# 02_-Thermistors.net
KiCad netlist of a schematic drawn in Altium Designer
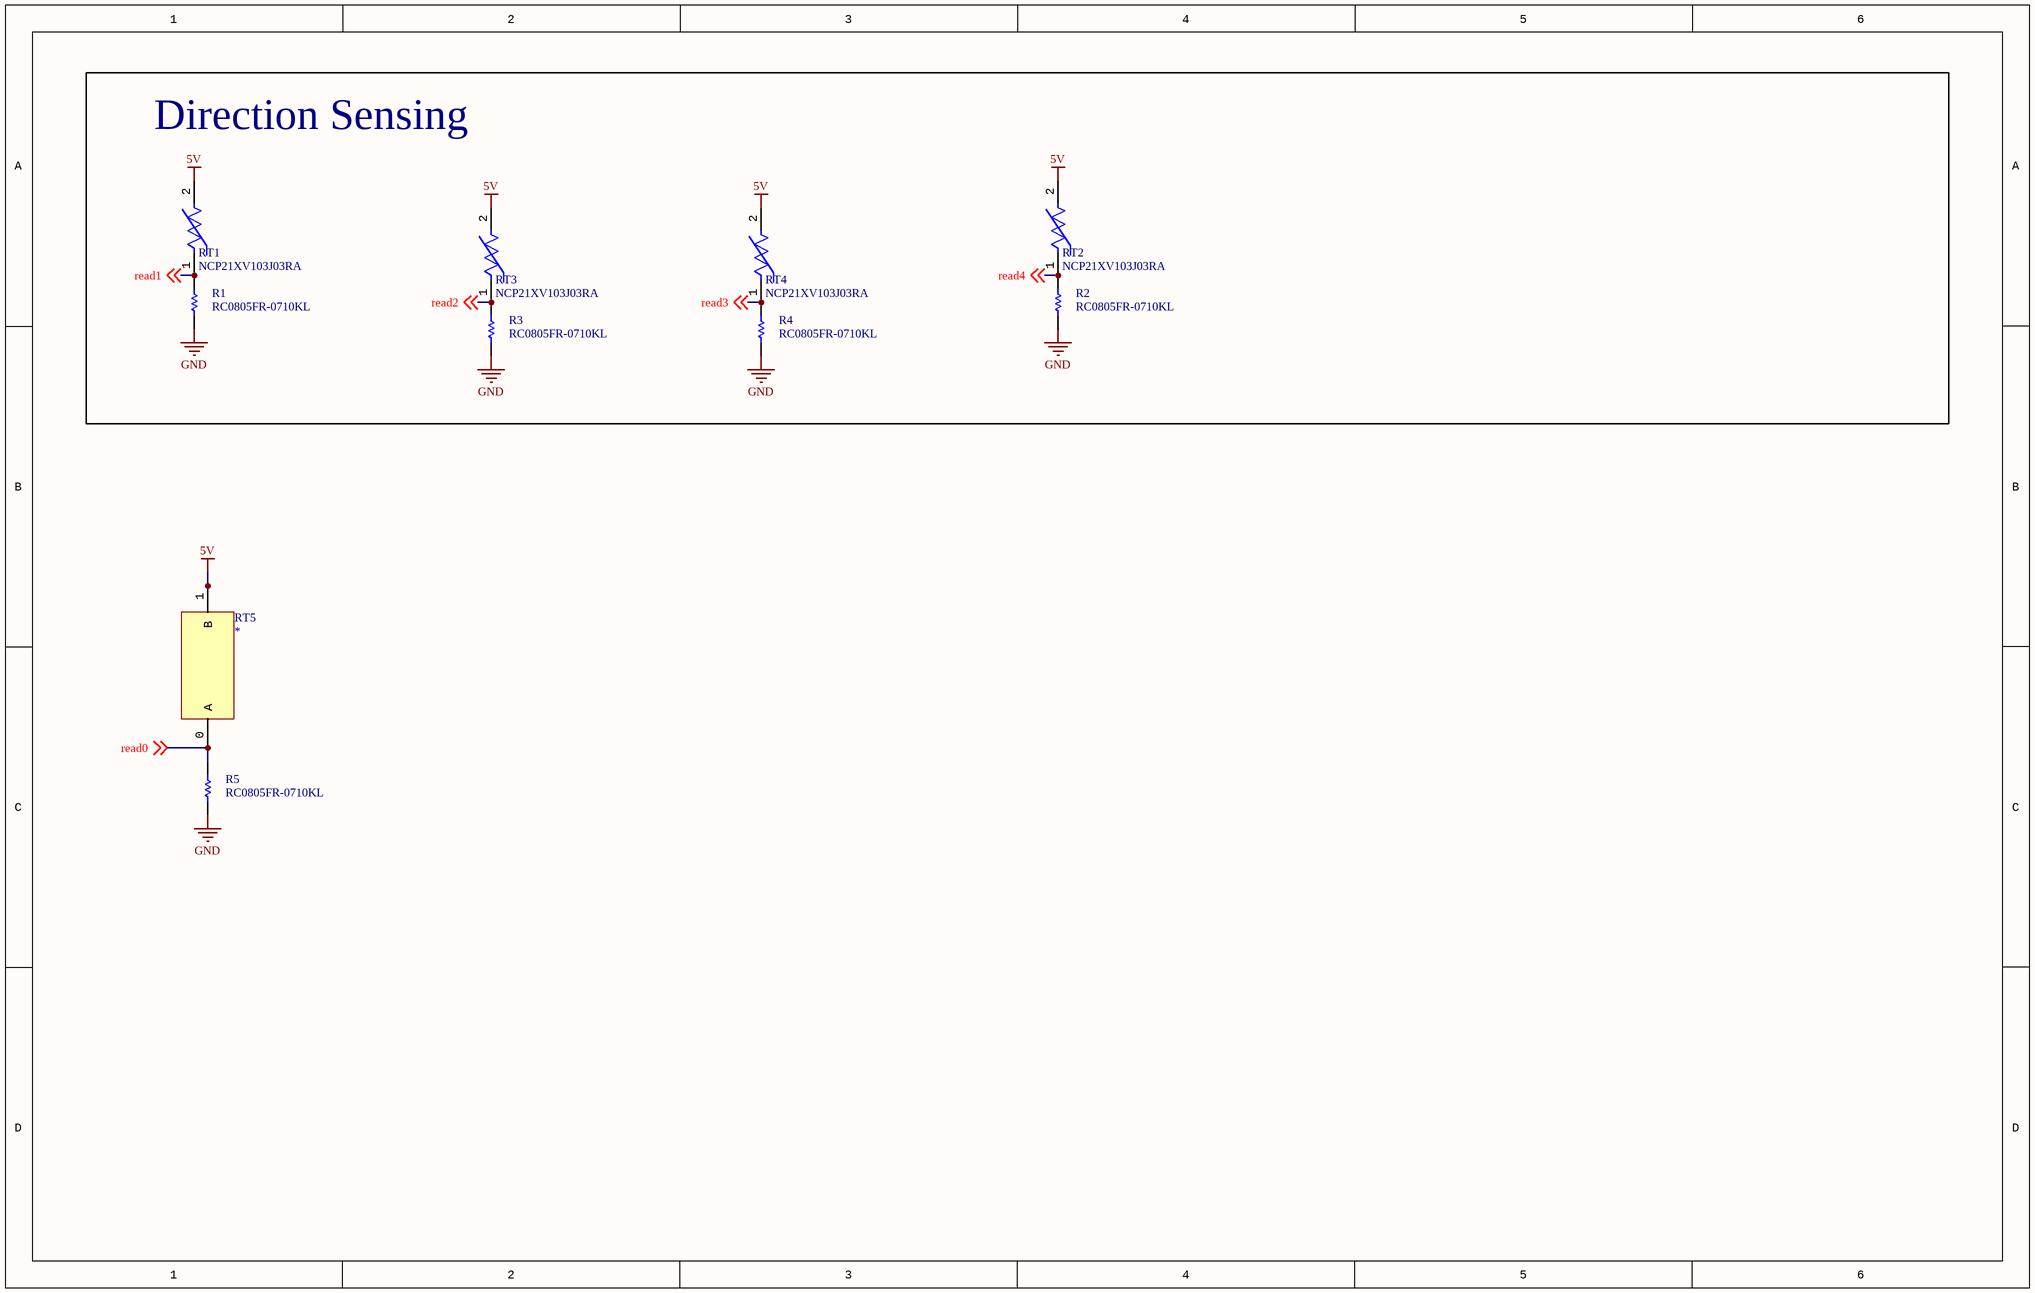
[diagram p0: [02]-Thermistors.SchDoc]

(export (version "E")
  (design (tool "Eeschema 10.0.6"))
  (components
    (comp (ref "R1")
      (value "RC0805FR-0710KL")
      (footprint "RESC2013X60X35LL10T20")
      (description "Chip Resistor, 10 KOhm, +/- 1%, 0.125 W, -55 to 155 degC, 0805 (2012 Metric), RoHS, Tape and Reel")
      (fields (field (name "MANUFACTURER") "Yageo"))
      (libsource (lib "Altium Content Vault") (part "RES-2"))
    )
    (comp (ref "R2")
      (value "RC0805FR-0710KL")
      (footprint "RESC2013X60X35LL10T20")
      (description "Chip Resistor, 10 KOhm, +/- 1%, 0.125 W, -55 to 155 degC, 0805 (2012 Metric), RoHS, Tape and Reel")
      (fields (field (name "MANUFACTURER") "Yageo"))
      (libsource (lib "Altium Content Vault") (part "RES-2"))
    )
    (comp (ref "R3")
      (value "RC0805FR-0710KL")
      (footprint "RESC2013X60X35LL10T20")
      (description "Chip Resistor, 10 KOhm, +/- 1%, 0.125 W, -55 to 155 degC, 0805 (2012 Metric), RoHS, Tape and Reel")
      (fields (field (name "MANUFACTURER") "Yageo"))
      (libsource (lib "Altium Content Vault") (part "RES-2"))
    )
    (comp (ref "R4")
      (value "RC0805FR-0710KL")
      (footprint "RESC2013X60X35LL10T20")
      (description "Chip Resistor, 10 KOhm, +/- 1%, 0.125 W, -55 to 155 degC, 0805 (2012 Metric), RoHS, Tape and Reel")
      (fields (field (name "MANUFACTURER") "Yageo"))
      (libsource (lib "Altium Content Vault") (part "RES-2"))
    )
    (comp (ref "R5")
      (value "RC0805FR-0710KL")
      (footprint "RESC2013X60X35LL10T20")
      (description "Chip Resistor, 10 KOhm, +/- 1%, 0.125 W, -55 to 155 degC, 0805 (2012 Metric), RoHS, Tape and Reel")
      (fields (field (name "MANUFACTURER") "Yageo"))
      (libsource (lib "Altium Content Vault") (part "RES-2"))
    )
    (comp (ref "RT1")
      (value "NCP21XV103J03RA")
      (footprint "FP-NCP21-0_2-IPC_C")
      (description "THERMISTOR NTC 10KOHM 3900K 0805")
      (fields (field (name "TOLERANCE") "5%"))
      (libsource (lib "Altium Content Vault") (part "3b148a6ebabc5fb4d708a66c052d352"))
    )
    (comp (ref "RT2")
      (value "NCP21XV103J03RA")
      (footprint "FP-NCP21-0_2-IPC_C")
      (description "THERMISTOR NTC 10KOHM 3900K 0805")
      (fields (field (name "TOLERANCE") "5%"))
      (libsource (lib "Altium Content Vault") (part "3b148a6ebabc5fb4d708a66c052d352"))
    )
    (comp (ref "RT3")
      (value "NCP21XV103J03RA")
      (footprint "FP-NCP21-0_2-IPC_C")
      (description "THERMISTOR NTC 10KOHM 3900K 0805")
      (fields (field (name "TOLERANCE") "5%"))
      (libsource (lib "Altium Content Vault") (part "3b148a6ebabc5fb4d708a66c052d352"))
    )
    (comp (ref "RT4")
      (value "NCP21XV103J03RA")
      (footprint "FP-NCP21-0_2-IPC_C")
      (description "THERMISTOR NTC 10KOHM 3900K 0805")
      (fields (field (name "TOLERANCE") "5%"))
      (libsource (lib "Altium Content Vault") (part "3b148a6ebabc5fb4d708a66c052d352"))
    )
    (comp (ref "RT5") (value "*") (footprint "thermistor") (libsource (lib "Schlib1") (part "thermistor")))
  )
  (nets
    (net (code "1") (name "5V") (class "Default")
      (node (ref "RT1") (pin "2") (pinfunction "2_2") (pintype "passive"))
      (node (ref "RT2") (pin "2") (pinfunction "2_2") (pintype "passive"))
      (node (ref "RT3") (pin "2") (pinfunction "2_2") (pintype "passive"))
      (node (ref "RT4") (pin "2") (pinfunction "2_2") (pintype "passive"))
      (node (ref "RT5") (pin "1") (pinfunction "B_1") (pintype "passive"))
    )
    (net (code "2") (name "GND") (class "Default")
      (node (ref "R1") (pin "1") (pinfunction "1_1") (pintype "passive"))
      (node (ref "R2") (pin "1") (pinfunction "1_1") (pintype "passive"))
      (node (ref "R3") (pin "1") (pinfunction "1_1") (pintype "passive"))
      (node (ref "R4") (pin "1") (pinfunction "1_1") (pintype "passive"))
      (node (ref "R5") (pin "1") (pinfunction "1_1") (pintype "passive"))
    )
    (net (code "3") (name "read0") (class "Default")
      (node (ref "R5") (pin "2") (pinfunction "2_2") (pintype "passive"))
      (node (ref "RT5") (pin "0") (pinfunction "A_0") (pintype "passive"))
    )
    (net (code "4") (name "read1") (class "Default")
      (node (ref "R1") (pin "2") (pinfunction "2_2") (pintype "passive"))
      (node (ref "RT1") (pin "1") (pinfunction "1_1") (pintype "passive"))
    )
    (net (code "5") (name "read2") (class "Default")
      (node (ref "R3") (pin "2") (pinfunction "2_2") (pintype "passive"))
      (node (ref "RT3") (pin "1") (pinfunction "1_1") (pintype "passive"))
    )
    (net (code "6") (name "read3") (class "Default")
      (node (ref "R4") (pin "2") (pinfunction "2_2") (pintype "passive"))
      (node (ref "RT4") (pin "1") (pinfunction "1_1") (pintype "passive"))
    )
    (net (code "7") (name "read4") (class "Default")
      (node (ref "R2") (pin "2") (pinfunction "2_2") (pintype "passive"))
      (node (ref "RT2") (pin "1") (pinfunction "1_1") (pintype "passive"))
    )
  )
)
